# Battery_PCB_8x4_Rev.net
KiCad netlist of a schematic drawn in Altium Designer
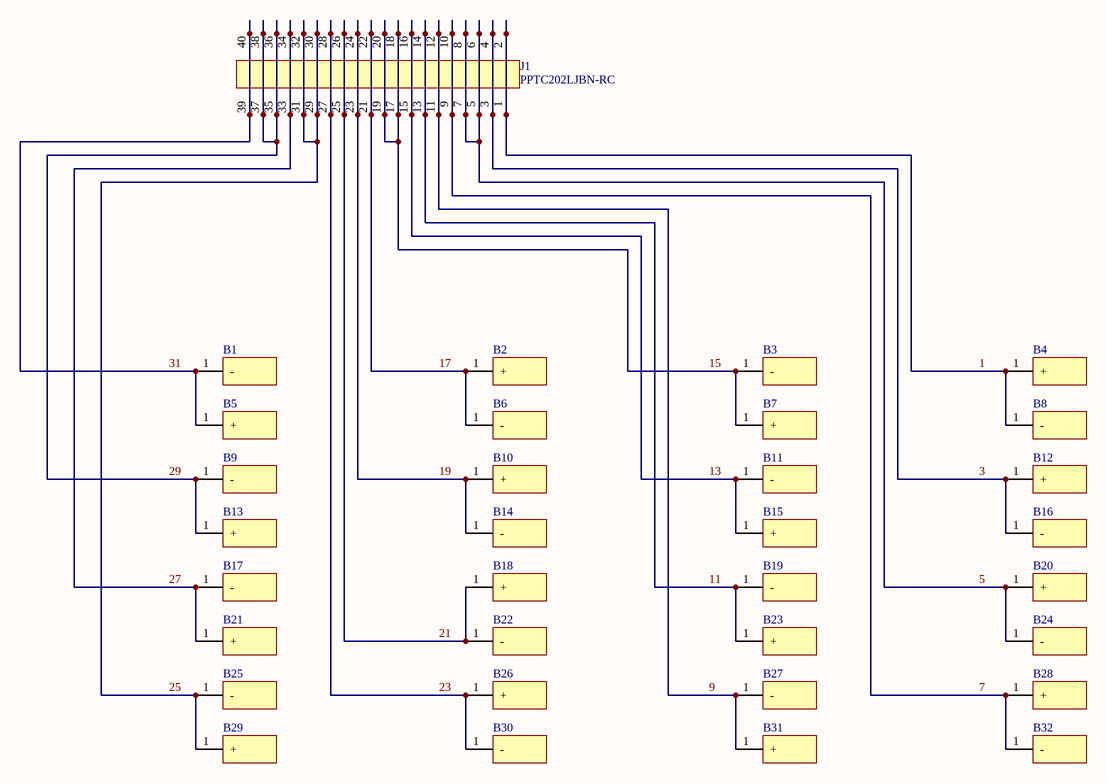
[diagram p0: Battery PCB 8x4 Rev.SchDoc]

(export (version "E")
  (design (tool "Eeschema 10.0.6"))
  (components
    (comp (ref "B1")
      (value "Negative side of battery")
      (footprint "BF_BATT_N")
      (libsource (lib "Bad-Fox") (part "BF_BATT_N"))
    )
    (comp (ref "B2")
      (value "Positive side of battery")
      (footprint "BF_BATT_P")
      (libsource (lib "Bad-Fox") (part "BF_BATT_P"))
    )
    (comp (ref "B3")
      (value "Negative side of battery")
      (footprint "BF_BATT_N")
      (libsource (lib "Bad-Fox") (part "BF_BATT_N"))
    )
    (comp (ref "B4")
      (value "Positive side of battery")
      (footprint "BF_BATT_P")
      (libsource (lib "Bad-Fox") (part "BF_BATT_P"))
    )
    (comp (ref "B5")
      (value "Positive side of battery")
      (footprint "BF_BATT_P")
      (libsource (lib "Bad-Fox") (part "BF_BATT_P"))
    )
    (comp (ref "B6")
      (value "Negative side of battery")
      (footprint "BF_BATT_N")
      (libsource (lib "Bad-Fox") (part "BF_BATT_N"))
    )
    (comp (ref "B7")
      (value "Positive side of battery")
      (footprint "BF_BATT_P")
      (libsource (lib "Bad-Fox") (part "BF_BATT_P"))
    )
    (comp (ref "B8")
      (value "Negative side of battery")
      (footprint "BF_BATT_N")
      (libsource (lib "Bad-Fox") (part "BF_BATT_N"))
    )
    (comp (ref "B9")
      (value "Negative side of battery")
      (footprint "BF_BATT_N")
      (libsource (lib "Bad-Fox") (part "BF_BATT_N"))
    )
    (comp (ref "B10")
      (value "Positive side of battery")
      (footprint "BF_BATT_P")
      (libsource (lib "Bad-Fox") (part "BF_BATT_P"))
    )
    (comp (ref "B11")
      (value "Negative side of battery")
      (footprint "BF_BATT_N")
      (libsource (lib "Bad-Fox") (part "BF_BATT_N"))
    )
    (comp (ref "B12")
      (value "Positive side of battery")
      (footprint "BF_BATT_P")
      (libsource (lib "Bad-Fox") (part "BF_BATT_P"))
    )
    (comp (ref "B13")
      (value "Positive side of battery")
      (footprint "BF_BATT_P")
      (libsource (lib "Bad-Fox") (part "BF_BATT_P"))
    )
    (comp (ref "B14")
      (value "Negative side of battery")
      (footprint "BF_BATT_N")
      (libsource (lib "Bad-Fox") (part "BF_BATT_N"))
    )
    (comp (ref "B15")
      (value "Positive side of battery")
      (footprint "BF_BATT_P")
      (libsource (lib "Bad-Fox") (part "BF_BATT_P"))
    )
    (comp (ref "B16")
      (value "Negative side of battery")
      (footprint "BF_BATT_N")
      (libsource (lib "Bad-Fox") (part "BF_BATT_N"))
    )
    (comp (ref "B17")
      (value "Negative side of battery")
      (footprint "BF_BATT_N")
      (libsource (lib "Bad-Fox") (part "BF_BATT_N"))
    )
    (comp (ref "B18")
      (value "Positive side of battery")
      (footprint "BF_BATT_P")
      (libsource (lib "Bad-Fox") (part "BF_BATT_P"))
    )
    (comp (ref "B19")
      (value "Negative side of battery")
      (footprint "BF_BATT_N")
      (libsource (lib "Bad-Fox") (part "BF_BATT_N"))
    )
    (comp (ref "B20")
      (value "Positive side of battery")
      (footprint "BF_BATT_P")
      (libsource (lib "Bad-Fox") (part "BF_BATT_P"))
    )
    (comp (ref "B21")
      (value "Positive side of battery")
      (footprint "BF_BATT_P")
      (libsource (lib "Bad-Fox") (part "BF_BATT_P"))
    )
    (comp (ref "B22")
      (value "Negative side of battery")
      (footprint "BF_BATT_N")
      (libsource (lib "Bad-Fox") (part "BF_BATT_N"))
    )
    (comp (ref "B23")
      (value "Positive side of battery")
      (footprint "BF_BATT_P")
      (libsource (lib "Bad-Fox") (part "BF_BATT_P"))
    )
    (comp (ref "B24")
      (value "Negative side of battery")
      (footprint "BF_BATT_N")
      (libsource (lib "Bad-Fox") (part "BF_BATT_N"))
    )
    (comp (ref "B25")
      (value "Negative side of battery")
      (footprint "BF_BATT_N")
      (libsource (lib "Bad-Fox") (part "BF_BATT_N"))
    )
    (comp (ref "B26")
      (value "Positive side of battery")
      (footprint "BF_BATT_P")
      (libsource (lib "Bad-Fox") (part "BF_BATT_P"))
    )
    (comp (ref "B27")
      (value "Negative side of battery")
      (footprint "BF_BATT_N")
      (libsource (lib "Bad-Fox") (part "BF_BATT_N"))
    )
    (comp (ref "B28")
      (value "Positive side of battery")
      (footprint "BF_BATT_P")
      (libsource (lib "Bad-Fox") (part "BF_BATT_P"))
    )
    (comp (ref "B29")
      (value "Positive side of battery")
      (footprint "BF_BATT_P")
      (libsource (lib "Bad-Fox") (part "BF_BATT_P"))
    )
    (comp (ref "B30")
      (value "Negative side of battery")
      (footprint "BF_BATT_N")
      (libsource (lib "Bad-Fox") (part "BF_BATT_N"))
    )
    (comp (ref "B31")
      (value "Positive side of battery")
      (footprint "BF_BATT_P")
      (libsource (lib "Bad-Fox") (part "BF_BATT_P"))
    )
    (comp (ref "B32")
      (value "Negative side of battery")
      (footprint "BF_BATT_N")
      (libsource (lib "Bad-Fox") (part "BF_BATT_N"))
    )
    (comp (ref "J1")
      (value "PPTC202LJBN-RC")
      (footprint "PPTC202LJBN-RC")
      (description "Conn Recept 40Pos 0.1\" dual row TH RA")
      (fields (field (name "MFG") "Sullins Connector Solutions"))
      (libsource (lib "Bad-Fox") (part "PPTC202LJBN-RC"))
    )
  )
  (nets
    (net (code "1") (name "/1") (class "Default")
      (node (ref "B4") (pin "1") (pinfunction "+_1") (pintype "passive"))
      (node (ref "B8") (pin "1") (pinfunction "-_1") (pintype "passive"))
      (node (ref "J1") (pin "1") (pintype "passive"))
      (node (ref "J1") (pin "2") (pintype "passive"))
    )
    (net (code "2") (name "/3") (class "Default")
      (node (ref "B12") (pin "1") (pinfunction "+_1") (pintype "passive"))
      (node (ref "B16") (pin "1") (pinfunction "-_1") (pintype "passive"))
      (node (ref "J1") (pin "3") (pintype "passive"))
      (node (ref "J1") (pin "4") (pintype "passive"))
    )
    (net (code "3") (name "/5") (class "Default")
      (node (ref "B20") (pin "1") (pinfunction "+_1") (pintype "passive"))
      (node (ref "B24") (pin "1") (pinfunction "-_1") (pintype "passive"))
      (node (ref "J1") (pin "5") (pintype "passive"))
      (node (ref "J1") (pin "6") (pintype "passive"))
      (node (ref "J1") (pin "7") (pintype "passive"))
      (node (ref "J1") (pin "8") (pintype "passive"))
    )
    (net (code "4") (name "/7") (class "Default")
      (node (ref "B28") (pin "1") (pinfunction "+_1") (pintype "passive"))
      (node (ref "B32") (pin "1") (pinfunction "-_1") (pintype "passive"))
      (node (ref "J1") (pin "10") (pintype "passive"))
      (node (ref "J1") (pin "9") (pintype "passive"))
    )
    (net (code "5") (name "/9") (class "Default")
      (node (ref "B27") (pin "1") (pinfunction "-_1") (pintype "passive"))
      (node (ref "B31") (pin "1") (pinfunction "+_1") (pintype "passive"))
      (node (ref "J1") (pin "11") (pintype "passive"))
      (node (ref "J1") (pin "12") (pintype "passive"))
    )
    (net (code "6") (name "/11") (class "Default")
      (node (ref "B19") (pin "1") (pinfunction "-_1") (pintype "passive"))
      (node (ref "B23") (pin "1") (pinfunction "+_1") (pintype "passive"))
      (node (ref "J1") (pin "13") (pintype "passive"))
      (node (ref "J1") (pin "14") (pintype "passive"))
    )
    (net (code "7") (name "/13") (class "Default")
      (node (ref "B11") (pin "1") (pinfunction "-_1") (pintype "passive"))
      (node (ref "B15") (pin "1") (pinfunction "+_1") (pintype "passive"))
      (node (ref "J1") (pin "15") (pintype "passive"))
      (node (ref "J1") (pin "16") (pintype "passive"))
    )
    (net (code "8") (name "/15") (class "Default")
      (node (ref "B3") (pin "1") (pinfunction "-_1") (pintype "passive"))
      (node (ref "B7") (pin "1") (pinfunction "+_1") (pintype "passive"))
      (node (ref "J1") (pin "17") (pintype "passive"))
      (node (ref "J1") (pin "18") (pintype "passive"))
      (node (ref "J1") (pin "19") (pintype "passive"))
      (node (ref "J1") (pin "20") (pintype "passive"))
    )
    (net (code "9") (name "/17") (class "Default")
      (node (ref "B2") (pin "1") (pinfunction "+_1") (pintype "passive"))
      (node (ref "B6") (pin "1") (pinfunction "-_1") (pintype "passive"))
      (node (ref "J1") (pin "21") (pintype "passive"))
      (node (ref "J1") (pin "22") (pintype "passive"))
    )
    (net (code "10") (name "/19") (class "Default")
      (node (ref "B10") (pin "1") (pinfunction "+_1") (pintype "passive"))
      (node (ref "B14") (pin "1") (pinfunction "-_1") (pintype "passive"))
      (node (ref "J1") (pin "23") (pintype "passive"))
      (node (ref "J1") (pin "24") (pintype "passive"))
    )
    (net (code "11") (name "/21") (class "Default")
      (node (ref "B18") (pin "1") (pinfunction "+_1") (pintype "passive"))
      (node (ref "B22") (pin "1") (pinfunction "-_1") (pintype "passive"))
      (node (ref "J1") (pin "25") (pintype "passive"))
      (node (ref "J1") (pin "26") (pintype "passive"))
    )
    (net (code "12") (name "/23") (class "Default")
      (node (ref "B26") (pin "1") (pinfunction "+_1") (pintype "passive"))
      (node (ref "B30") (pin "1") (pinfunction "-_1") (pintype "passive"))
      (node (ref "J1") (pin "27") (pintype "passive"))
      (node (ref "J1") (pin "28") (pintype "passive"))
    )
    (net (code "13") (name "/25") (class "Default")
      (node (ref "B25") (pin "1") (pinfunction "-_1") (pintype "passive"))
      (node (ref "B29") (pin "1") (pinfunction "+_1") (pintype "passive"))
      (node (ref "J1") (pin "29") (pintype "passive"))
      (node (ref "J1") (pin "30") (pintype "passive"))
      (node (ref "J1") (pin "31") (pintype "passive"))
      (node (ref "J1") (pin "32") (pintype "passive"))
    )
    (net (code "14") (name "/27") (class "Default")
      (node (ref "B17") (pin "1") (pinfunction "-_1") (pintype "passive"))
      (node (ref "B21") (pin "1") (pinfunction "+_1") (pintype "passive"))
      (node (ref "J1") (pin "33") (pintype "passive"))
      (node (ref "J1") (pin "34") (pintype "passive"))
    )
    (net (code "15") (name "/29") (class "Default")
      (node (ref "B13") (pin "1") (pinfunction "+_1") (pintype "passive"))
      (node (ref "B9") (pin "1") (pinfunction "-_1") (pintype "passive"))
      (node (ref "J1") (pin "35") (pintype "passive"))
      (node (ref "J1") (pin "36") (pintype "passive"))
      (node (ref "J1") (pin "37") (pintype "passive"))
      (node (ref "J1") (pin "38") (pintype "passive"))
    )
    (net (code "16") (name "/31") (class "Default")
      (node (ref "B1") (pin "1") (pinfunction "-_1") (pintype "passive"))
      (node (ref "B5") (pin "1") (pinfunction "+_1") (pintype "passive"))
      (node (ref "J1") (pin "39") (pintype "passive"))
      (node (ref "J1") (pin "40") (pintype "passive"))
    )
  )
)
